# pmic_tps65263_buck.net
KiCad netlist of a schematic drawn in Altium Designer
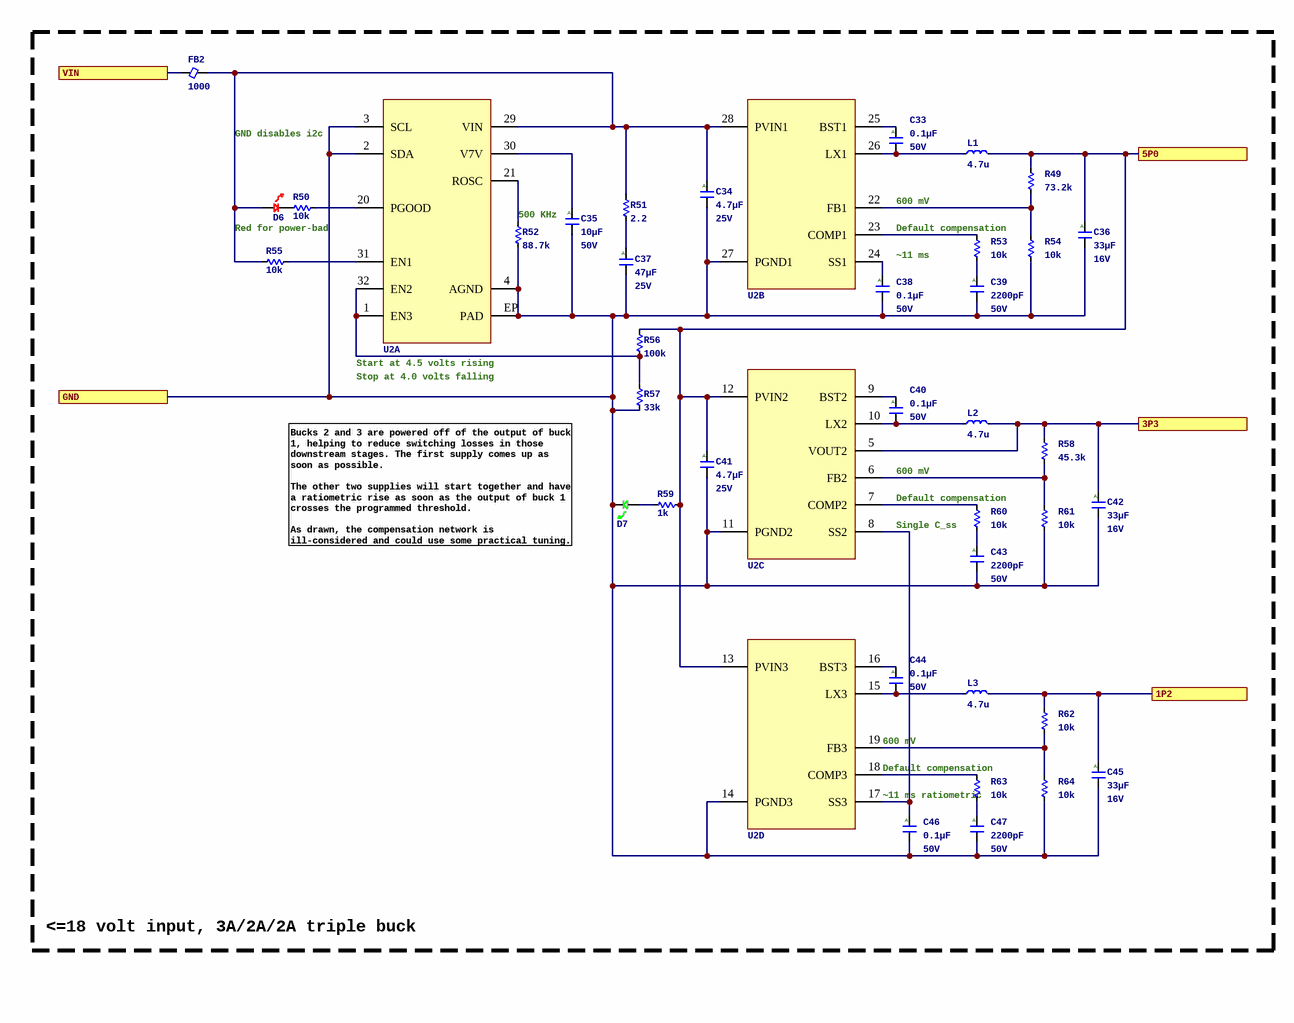
[diagram p0: pmic_tps65263_buck.SchDoc]

(export (version "E")
  (design (tool "Eeschema 10.0.6"))
  (components
    (comp (ref "C33")
      (value "CGA2B3X7R1H104M050BB")
      (footprint "C0402_0.55MM")
      (description "CAP CER 0.1UF 50V X7R 0402")
      (fields
        (field (name "CAPACITANCE") "0.1µF")
        (field (name "VOLTAGE - RATED") "50V")
        (field (name "TOLERANCE") "±20%")
        (field (name "MANUFACTURER") "TDK Corporation")
      )
      (libsource (lib "sscp") (part "__template_cap_auto"))
    )
    (comp (ref "C34")
      (value "CGA4J1X7R1E475K125AC")
      (footprint "C0805_1.45MM")
      (description "CAP CER 4.7UF 25V X7R 0805")
      (fields
        (field (name "CAPACITANCE") "4.7µF")
        (field (name "VOLTAGE - RATED") "25V")
        (field (name "TOLERANCE") "±10%")
        (field (name "MANUFACTURER") "TDK Corporation")
      )
      (libsource (lib "sscp") (part "__template_cap_auto"))
    )
    (comp (ref "C35")
      (value "CGA5L1X7R1H106K160AC")
      (footprint "C1206_1.90MM")
      (description "CAP CER 10UF 50V X7R 1206")
      (fields
        (field (name "CAPACITANCE") "10µF")
        (field (name "VOLTAGE - RATED") "50V")
        (field (name "TOLERANCE") "±10%")
        (field (name "MANUFACTURER") "TDK Corporation")
      )
      (libsource (lib "sscp") (part "__template_cap_auto"))
    )
    (comp (ref "C36")
      (value "CGA8P1X7R1C336M250KC")
      (footprint "C1812_2.50MM")
      (description "CAP CER 33UF 16V X7R 1812")
      (fields
        (field (name "CAPACITANCE") "33µF")
        (field (name "VOLTAGE - RATED") "16V")
        (field (name "TOLERANCE") "±20%")
        (field (name "MANUFACTURER") "TDK Corporation")
      )
      (libsource (lib "sscp") (part "__template_cap_auto"))
    )
    (comp (ref "C37")
      (value "CGA9N3X7R1E476M230KB")
      (footprint "C2220_2.50MM")
      (description "CAP CER 47UF 25V X7R 2220")
      (fields
        (field (name "CAPACITANCE") "47µF")
        (field (name "VOLTAGE - RATED") "25V")
        (field (name "TOLERANCE") "±20%")
        (field (name "MANUFACTURER") "TDK Corporation")
      )
      (libsource (lib "sscp") (part "__template_cap_auto"))
    )
    (comp (ref "C38")
      (value "CGA2B3X7R1H104M050BB")
      (footprint "C0402_0.55MM")
      (description "CAP CER 0.1UF 50V X7R 0402")
      (fields
        (field (name "CAPACITANCE") "0.1µF")
        (field (name "VOLTAGE - RATED") "50V")
        (field (name "TOLERANCE") "±20%")
        (field (name "MANUFACTURER") "TDK Corporation")
      )
      (libsource (lib "sscp") (part "__template_cap_auto"))
    )
    (comp (ref "C39")
      (value "CGA2B2X7R1H222M050BA")
      (footprint "C0402_0.55MM")
      (description "CAP CER 2200PF 50V X7R 0402")
      (fields
        (field (name "CAPACITANCE") "2200pF")
        (field (name "VOLTAGE - RATED") "50V")
        (field (name "TOLERANCE") "±20%")
        (field (name "MANUFACTURER") "TDK Corporation")
      )
      (libsource (lib "sscp") (part "__template_cap_auto"))
    )
    (comp (ref "C40")
      (value "CGA2B3X7R1H104M050BB")
      (footprint "C0402_0.55MM")
      (description "CAP CER 0.1UF 50V X7R 0402")
      (fields
        (field (name "CAPACITANCE") "0.1µF")
        (field (name "VOLTAGE - RATED") "50V")
        (field (name "TOLERANCE") "±20%")
        (field (name "MANUFACTURER") "TDK Corporation")
      )
      (libsource (lib "sscp") (part "__template_cap_auto"))
    )
    (comp (ref "C41")
      (value "CGA4J1X7R1E475K125AC")
      (footprint "C0805_1.45MM")
      (description "CAP CER 4.7UF 25V X7R 0805")
      (fields
        (field (name "CAPACITANCE") "4.7µF")
        (field (name "VOLTAGE - RATED") "25V")
        (field (name "TOLERANCE") "±10%")
        (field (name "MANUFACTURER") "TDK Corporation")
      )
      (libsource (lib "sscp") (part "__template_cap_auto"))
    )
    (comp (ref "C42")
      (value "CGA8P1X7R1C336M250KC")
      (footprint "C1812_2.50MM")
      (description "CAP CER 33UF 16V X7R 1812")
      (fields
        (field (name "CAPACITANCE") "33µF")
        (field (name "VOLTAGE - RATED") "16V")
        (field (name "TOLERANCE") "±20%")
        (field (name "MANUFACTURER") "TDK Corporation")
      )
      (libsource (lib "sscp") (part "__template_cap_auto"))
    )
    (comp (ref "C43")
      (value "CGA2B2X7R1H222M050BA")
      (footprint "C0402_0.55MM")
      (description "CAP CER 2200PF 50V X7R 0402")
      (fields
        (field (name "CAPACITANCE") "2200pF")
        (field (name "VOLTAGE - RATED") "50V")
        (field (name "TOLERANCE") "±20%")
        (field (name "MANUFACTURER") "TDK Corporation")
      )
      (libsource (lib "sscp") (part "__template_cap_auto"))
    )
    (comp (ref "C44")
      (value "CGA2B3X7R1H104M050BB")
      (footprint "C0402_0.55MM")
      (description "CAP CER 0.1UF 50V X7R 0402")
      (fields
        (field (name "CAPACITANCE") "0.1µF")
        (field (name "VOLTAGE - RATED") "50V")
        (field (name "TOLERANCE") "±20%")
        (field (name "MANUFACTURER") "TDK Corporation")
      )
      (libsource (lib "sscp") (part "__template_cap_auto"))
    )
    (comp (ref "C45")
      (value "CGA8P1X7R1C336M250KC")
      (footprint "C1812_2.50MM")
      (description "CAP CER 33UF 16V X7R 1812")
      (fields
        (field (name "CAPACITANCE") "33µF")
        (field (name "VOLTAGE - RATED") "16V")
        (field (name "TOLERANCE") "±20%")
        (field (name "MANUFACTURER") "TDK Corporation")
      )
      (libsource (lib "sscp") (part "__template_cap_auto"))
    )
    (comp (ref "C46")
      (value "CGA2B3X7R1H104M050BB")
      (footprint "C0402_0.55MM")
      (description "CAP CER 0.1UF 50V X7R 0402")
      (fields
        (field (name "CAPACITANCE") "0.1µF")
        (field (name "VOLTAGE - RATED") "50V")
        (field (name "TOLERANCE") "±20%")
        (field (name "MANUFACTURER") "TDK Corporation")
      )
      (libsource (lib "sscp") (part "__template_cap_auto"))
    )
    (comp (ref "C47")
      (value "CGA2B2X7R1H222M050BA")
      (footprint "C0402_0.55MM")
      (description "CAP CER 2200PF 50V X7R 0402")
      (fields
        (field (name "CAPACITANCE") "2200pF")
        (field (name "VOLTAGE - RATED") "50V")
        (field (name "TOLERANCE") "±20%")
        (field (name "MANUFACTURER") "TDK Corporation")
      )
      (libsource (lib "sscp") (part "__template_cap_auto"))
    )
    (comp (ref "D6")
      (value "LTST-C190KRKT")
      (footprint "LED_0603P_RED")
      (description "LED SUPER RED CLEAR 0603 SMD")
      (fields (field (name "MANUFACTURER") "Lite-On Inc"))
      (libsource (lib "SSCP") (part "LED_0603_RED_LTST-C190KRKT"))
    )
    (comp (ref "D7")
      (value "LTST-C190GKT")
      (footprint "LED_0603P_GREEN")
      (description "LED GREEN CLEAR 0603 SMD")
      (fields (field (name "MANUFACTURER") "Lite-On Inc"))
      (libsource (lib "SSCP") (part "LED_0603_GREEN_LTST-C190GKT"))
    )
    (comp (ref "FB2")
      (value "MPZ2012S102AT000")
      (footprint "FB0805_1.05MM")
      (description "FERRITE BEAD 1 KOHM 0805 1LN")
      (fields
        (field (name "IMPEDANCE (OHMS @ 100MHZ)") "1000")
        (field (name "MANUFACTURER") "TDK Corporation")
      )
      (libsource (lib "sscp") (part "__template_ferrite"))
    )
    (comp (ref "L1")
      (value "74438357047")
      (footprint "WE-MAPI_4030")
      (description "FIXED IND 4.7UH 3.9A 44 MOHM SMD")
      (fields
        (field (name "INDUCTANCE") "4.7u")
        (field (name "TOLERANCE") "±20%")
        (field (name "MANUFACTURER") "Würth Elektronik")
      )
      (libsource (lib "sscp") (part "__template_inductor"))
    )
    (comp (ref "L2")
      (value "74438357047")
      (footprint "WE-MAPI_4030")
      (description "FIXED IND 4.7UH 3.9A 44 MOHM SMD")
      (fields
        (field (name "INDUCTANCE") "4.7u")
        (field (name "TOLERANCE") "±20%")
        (field (name "MANUFACTURER") "Würth Elektronik")
      )
      (libsource (lib "sscp") (part "__template_inductor"))
    )
    (comp (ref "L3")
      (value "74438357047")
      (footprint "WE-MAPI_4030")
      (description "FIXED IND 4.7UH 3.9A 44 MOHM SMD")
      (fields
        (field (name "INDUCTANCE") "4.7u")
        (field (name "TOLERANCE") "±20%")
        (field (name "MANUFACTURER") "Würth Elektronik")
      )
      (libsource (lib "sscp") (part "__template_inductor"))
    )
    (comp (ref "R49")
      (value "ERJ-2RKF7322X")
      (footprint "R0402_0.40MM")
      (description "RES SMD 73.2K OHM 1% 1/10W 0402")
      (fields
        (field (name "RESISTANCE") "73.2k")
        (field (name "TOLERANCE") "±1%")
        (field (name "MANUFACTURER") "Panasonic Electronic Components")
      )
      (libsource (lib "sscp") (part "__template_resistor"))
    )
    (comp (ref "R50")
      (value "ERJ-2RKF1002X")
      (footprint "R0402_0.40MM")
      (description "RES SMD 10K OHM 1% 1/10W 0402")
      (fields
        (field (name "RESISTANCE") "10k")
        (field (name "TOLERANCE") "±1%")
        (field (name "MANUFACTURER") "Panasonic Electronic Components")
      )
      (libsource (lib "sscp") (part "__template_resistor"))
    )
    (comp (ref "R51")
      (value "ERJ-6DQF2R2V")
      (footprint "R0805_0.70MM")
      (description "RES SMD 2.2 OHM 1% 1/2W 0805")
      (fields
        (field (name "RESISTANCE") "2.2")
        (field (name "TOLERANCE") "±1%")
        (field (name "MANUFACTURER") "Panasonic Electronic Components")
      )
      (libsource (lib "sscp") (part "__template_resistor"))
    )
    (comp (ref "R52")
      (value "ERJ-2RKF8872X")
      (footprint "R0402_0.40MM")
      (description "RES SMD 88.7K OHM 1% 1/10W 0402")
      (fields
        (field (name "RESISTANCE") "88.7k")
        (field (name "TOLERANCE") "±1%")
        (field (name "MANUFACTURER") "Panasonic Electronic Components")
      )
      (libsource (lib "sscp") (part "__template_resistor"))
    )
    (comp (ref "R53")
      (value "ERJ-2RKF1002X")
      (footprint "R0402_0.40MM")
      (description "RES SMD 10K OHM 1% 1/10W 0402")
      (fields
        (field (name "RESISTANCE") "10k")
        (field (name "TOLERANCE") "±1%")
        (field (name "MANUFACTURER") "Panasonic Electronic Components")
      )
      (libsource (lib "sscp") (part "__template_resistor"))
    )
    (comp (ref "R54")
      (value "ERJ-2RKF1002X")
      (footprint "R0402_0.40MM")
      (description "RES SMD 10K OHM 1% 1/10W 0402")
      (fields
        (field (name "RESISTANCE") "10k")
        (field (name "TOLERANCE") "±1%")
        (field (name "MANUFACTURER") "Panasonic Electronic Components")
      )
      (libsource (lib "sscp") (part "__template_resistor"))
    )
    (comp (ref "R55")
      (value "ERJ-2RKF1002X")
      (footprint "R0402_0.40MM")
      (description "RES SMD 10K OHM 1% 1/10W 0402")
      (fields
        (field (name "RESISTANCE") "10k")
        (field (name "TOLERANCE") "±1%")
        (field (name "MANUFACTURER") "Panasonic Electronic Components")
      )
      (libsource (lib "sscp") (part "__template_resistor"))
    )
    (comp (ref "R56")
      (value "ERJ-2RKF1003X")
      (footprint "R0402_0.40MM")
      (description "RES SMD 100K OHM 1% 1/10W 0402")
      (fields
        (field (name "RESISTANCE") "100k")
        (field (name "TOLERANCE") "±1%")
        (field (name "MANUFACTURER") "Panasonic Electronic Components")
      )
      (libsource (lib "sscp") (part "__template_resistor"))
    )
    (comp (ref "R57")
      (value "ERJ-2RKF3302X")
      (footprint "R0402_0.40MM")
      (description "RES SMD 33K OHM 1% 1/10W 0402")
      (fields
        (field (name "RESISTANCE") "33k")
        (field (name "TOLERANCE") "±1%")
        (field (name "MANUFACTURER") "Panasonic Electronic Components")
      )
      (libsource (lib "sscp") (part "__template_resistor"))
    )
    (comp (ref "R58")
      (value "ERJ-2RKF4532X")
      (footprint "R0402_0.40MM")
      (description "RES SMD 45.3K OHM 1% 1/10W 0402")
      (fields
        (field (name "RESISTANCE") "45.3k")
        (field (name "TOLERANCE") "±1%")
        (field (name "MANUFACTURER") "Panasonic Electronic Components")
      )
      (libsource (lib "sscp") (part "__template_resistor"))
    )
    (comp (ref "R59")
      (value "~")
      (footprint "R0402_0.40MM")
      (description "RES SMD 1K OHM 1% 1/10W 0402")
      (fields (field (name "RESISTANCE") "1k") (field (name "TOLERANCE") "±1%"))
      (libsource (lib "sscp") (part "__template_resistor"))
    )
    (comp (ref "R60")
      (value "ERJ-2RKF1002X")
      (footprint "R0402_0.40MM")
      (description "RES SMD 10K OHM 1% 1/10W 0402")
      (fields
        (field (name "RESISTANCE") "10k")
        (field (name "TOLERANCE") "±1%")
        (field (name "MANUFACTURER") "Panasonic Electronic Components")
      )
      (libsource (lib "sscp") (part "__template_resistor"))
    )
    (comp (ref "R61")
      (value "ERJ-2RKF1002X")
      (footprint "R0402_0.40MM")
      (description "RES SMD 10K OHM 1% 1/10W 0402")
      (fields
        (field (name "RESISTANCE") "10k")
        (field (name "TOLERANCE") "±1%")
        (field (name "MANUFACTURER") "Panasonic Electronic Components")
      )
      (libsource (lib "sscp") (part "__template_resistor"))
    )
    (comp (ref "R62")
      (value "ERJ-2RKF1002X")
      (footprint "R0402_0.40MM")
      (description "RES SMD 10K OHM 1% 1/10W 0402")
      (fields
        (field (name "RESISTANCE") "10k")
        (field (name "TOLERANCE") "±1%")
        (field (name "MANUFACTURER") "Panasonic Electronic Components")
      )
      (libsource (lib "sscp") (part "__template_resistor"))
    )
    (comp (ref "R63")
      (value "ERJ-2RKF1002X")
      (footprint "R0402_0.40MM")
      (description "RES SMD 10K OHM 1% 1/10W 0402")
      (fields
        (field (name "RESISTANCE") "10k")
        (field (name "TOLERANCE") "±1%")
        (field (name "MANUFACTURER") "Panasonic Electronic Components")
      )
      (libsource (lib "sscp") (part "__template_resistor"))
    )
    (comp (ref "R64")
      (value "ERJ-2RKF1002X")
      (footprint "R0402_0.40MM")
      (description "RES SMD 10K OHM 1% 1/10W 0402")
      (fields
        (field (name "RESISTANCE") "10k")
        (field (name "TOLERANCE") "±1%")
        (field (name "MANUFACTURER") "Panasonic Electronic Components")
      )
      (libsource (lib "sscp") (part "__template_resistor"))
    )
    (comp (ref "U2")
      (value "TPS65263QRHBRQ1")
      (footprint "TI_RHB")
      (description "Switching Regulator, Current-mode, 3A, 2300kHz Switching Freq-Max, PQCC32")
      (fields (field (name "MANUFACTURER") "Texas Instruments"))
      (libsource (lib "SSCP") (part "BUCK_TPS65263QRHBRQ1"))
    )
  )
  (nets
    (net (code "1") (name "/1P2") (class "Default")
      (node (ref "C45") (pin "1") (pintype "passive"))
      (node (ref "L3") (pin "2") (pintype "passive"))
      (node (ref "R62") (pin "2") (pintype "passive"))
    )
    (net (code "2") (name "/3P3") (class "Default")
      (node (ref "C42") (pin "1") (pintype "passive"))
      (node (ref "L2") (pin "2") (pintype "passive"))
      (node (ref "R58") (pin "2") (pintype "passive"))
      (node (ref "U2") (pin "5") (pinfunction "VOUT2_5") (pintype "passive"))
    )
    (net (code "3") (name "/5P0") (class "Default")
      (node (ref "C36") (pin "1") (pintype "passive"))
      (node (ref "C41") (pin "1") (pintype "passive"))
      (node (ref "L1") (pin "2") (pintype "passive"))
      (node (ref "R49") (pin "2") (pintype "passive"))
      (node (ref "R56") (pin "2") (pintype "passive"))
      (node (ref "R59") (pin "1") (pintype "passive"))
      (node (ref "U2") (pin "12") (pinfunction "PVIN2_12") (pintype "passive"))
      (node (ref "U2") (pin "13") (pinfunction "PVIN3_13") (pintype "passive"))
    )
    (net (code "4") (name "/GND") (class "Default")
      (node (ref "C34") (pin "2") (pintype "passive"))
      (node (ref "C35") (pin "2") (pintype "passive"))
      (node (ref "C36") (pin "2") (pintype "passive"))
      (node (ref "C37") (pin "2") (pintype "passive"))
      (node (ref "C38") (pin "2") (pintype "passive"))
      (node (ref "C39") (pin "2") (pintype "passive"))
      (node (ref "C41") (pin "2") (pintype "passive"))
      (node (ref "C42") (pin "2") (pintype "passive"))
      (node (ref "C43") (pin "2") (pintype "passive"))
      (node (ref "C45") (pin "2") (pintype "passive"))
      (node (ref "C46") (pin "2") (pintype "passive"))
      (node (ref "C47") (pin "2") (pintype "passive"))
      (node (ref "D7") (pin "1") (pintype "passive"))
      (node (ref "R52") (pin "1") (pintype "passive"))
      (node (ref "R54") (pin "1") (pintype "passive"))
      (node (ref "R57") (pin "1") (pintype "passive"))
      (node (ref "R61") (pin "1") (pintype "passive"))
      (node (ref "R64") (pin "1") (pintype "passive"))
      (node (ref "U2") (pin "11") (pinfunction "PGND2_11") (pintype "passive"))
      (node (ref "U2") (pin "14") (pinfunction "PGND3_14") (pintype "passive"))
      (node (ref "U2") (pin "2") (pinfunction "SDA_2") (pintype "passive"))
      (node (ref "U2") (pin "27") (pinfunction "PGND1_27") (pintype "passive"))
      (node (ref "U2") (pin "3") (pinfunction "SCL_3") (pintype "passive"))
      (node (ref "U2") (pin "4") (pinfunction "AGND_4") (pintype "passive"))
      (node (ref "U2") (pin "EP") (pinfunction "PAD_EP") (pintype "passive"))
    )
    (net (code "5") (name "/VIN") (class "Default") (node (ref "FB2") (pin "1") (pintype "passive")))
    (net (code "6") (name "Net-(C37-Pad1)") (class "Default")
      (node (ref "C37") (pin "1") (pintype "passive"))
      (node (ref "R51") (pin "1") (pintype "passive"))
    )
    (net (code "7") (name "Net-(C39-Pad1)") (class "Default")
      (node (ref "C39") (pin "1") (pintype "passive"))
      (node (ref "R53") (pin "1") (pintype "passive"))
    )
    (net (code "8") (name "Net-(C43-Pad1)") (class "Default")
      (node (ref "C43") (pin "1") (pintype "passive"))
      (node (ref "R60") (pin "1") (pintype "passive"))
    )
    (net (code "9") (name "Net-(C47-Pad1)") (class "Default")
      (node (ref "C47") (pin "1") (pintype "passive"))
      (node (ref "R63") (pin "1") (pintype "passive"))
    )
    (net (code "10") (name "Net-(D6-Pad1)") (class "Default")
      (node (ref "D6") (pin "1") (pintype "passive"))
      (node (ref "R50") (pin "2") (pintype "passive"))
    )
    (net (code "11") (name "Net-(D7-Pad2)") (class "Default")
      (node (ref "D7") (pin "2") (pintype "passive"))
      (node (ref "R59") (pin "2") (pintype "passive"))
    )
    (net (code "12") (name "Net-(U2A-EN1)") (class "Default")
      (node (ref "R55") (pin "2") (pintype "passive"))
      (node (ref "U2") (pin "31") (pinfunction "EN1_31") (pintype "passive"))
    )
    (net (code "13") (name "Net-(U2A-EN2)") (class "Default")
      (node (ref "R56") (pin "1") (pintype "passive"))
      (node (ref "R57") (pin "2") (pintype "passive"))
      (node (ref "U2") (pin "1") (pinfunction "EN3_1") (pintype "passive"))
      (node (ref "U2") (pin "32") (pinfunction "EN2_32") (pintype "passive"))
    )
    (net (code "14") (name "Net-(U2A-PGOOD)") (class "Default")
      (node (ref "R50") (pin "1") (pintype "passive"))
      (node (ref "U2") (pin "20") (pinfunction "PGOOD_20") (pintype "passive"))
    )
    (net (code "15") (name "Net-(U2A-ROSC)") (class "Default")
      (node (ref "R52") (pin "2") (pintype "passive"))
      (node (ref "U2") (pin "21") (pinfunction "ROSC_21") (pintype "passive"))
    )
    (net (code "16") (name "Net-(U2A-V7V)") (class "Default")
      (node (ref "C35") (pin "1") (pintype "passive"))
      (node (ref "U2") (pin "30") (pinfunction "V7V_30") (pintype "passive"))
    )
    (net (code "17") (name "Net-(U2A-VIN)") (class "Default")
      (node (ref "C34") (pin "1") (pintype "passive"))
      (node (ref "D6") (pin "2") (pintype "passive"))
      (node (ref "FB2") (pin "2") (pintype "passive"))
      (node (ref "R51") (pin "2") (pintype "passive"))
      (node (ref "R55") (pin "1") (pintype "passive"))
      (node (ref "U2") (pin "28") (pinfunction "PVIN1_28") (pintype "passive"))
      (node (ref "U2") (pin "29") (pinfunction "VIN_29") (pintype "passive"))
    )
    (net (code "18") (name "Net-(U2B-BST1)") (class "Default")
      (node (ref "C33") (pin "1") (pintype "passive"))
      (node (ref "U2") (pin "25") (pinfunction "BST1_25") (pintype "passive"))
    )
    (net (code "19") (name "Net-(U2B-COMP1)") (class "Default")
      (node (ref "R53") (pin "2") (pintype "passive"))
      (node (ref "U2") (pin "23") (pinfunction "COMP1_23") (pintype "passive"))
    )
    (net (code "20") (name "Net-(U2B-FB1)") (class "Default")
      (node (ref "R49") (pin "1") (pintype "passive"))
      (node (ref "R54") (pin "2") (pintype "passive"))
      (node (ref "U2") (pin "22") (pinfunction "FB1_22") (pintype "passive"))
    )
    (net (code "21") (name "Net-(U2B-LX1)") (class "Default")
      (node (ref "C33") (pin "2") (pintype "passive"))
      (node (ref "L1") (pin "1") (pintype "passive"))
      (node (ref "U2") (pin "26") (pinfunction "LX1_26") (pintype "passive"))
    )
    (net (code "22") (name "Net-(U2B-SS1)") (class "Default")
      (node (ref "C38") (pin "1") (pintype "passive"))
      (node (ref "U2") (pin "24") (pinfunction "SS1_24") (pintype "passive"))
    )
    (net (code "23") (name "Net-(U2C-BST2)") (class "Default")
      (node (ref "C40") (pin "1") (pintype "passive"))
      (node (ref "U2") (pin "9") (pinfunction "BST2_9") (pintype "passive"))
    )
    (net (code "24") (name "Net-(U2C-COMP2)") (class "Default")
      (node (ref "R60") (pin "2") (pintype "passive"))
      (node (ref "U2") (pin "7") (pinfunction "COMP2_7") (pintype "passive"))
    )
    (net (code "25") (name "Net-(U2C-FB2)") (class "Default")
      (node (ref "R58") (pin "1") (pintype "passive"))
      (node (ref "R61") (pin "2") (pintype "passive"))
      (node (ref "U2") (pin "6") (pinfunction "FB2_6") (pintype "passive"))
    )
    (net (code "26") (name "Net-(U2C-LX2)") (class "Default")
      (node (ref "C40") (pin "2") (pintype "passive"))
      (node (ref "L2") (pin "1") (pintype "passive"))
      (node (ref "U2") (pin "10") (pinfunction "LX2_10") (pintype "passive"))
    )
    (net (code "27") (name "Net-(U2C-SS2)") (class "Default")
      (node (ref "C46") (pin "1") (pintype "passive"))
      (node (ref "U2") (pin "17") (pinfunction "SS3_17") (pintype "passive"))
      (node (ref "U2") (pin "8") (pinfunction "SS2_8") (pintype "passive"))
    )
    (net (code "28") (name "Net-(U2D-BST3)") (class "Default")
      (node (ref "C44") (pin "1") (pintype "passive"))
      (node (ref "U2") (pin "16") (pinfunction "BST3_16") (pintype "passive"))
    )
    (net (code "29") (name "Net-(U2D-COMP3)") (class "Default")
      (node (ref "R63") (pin "2") (pintype "passive"))
      (node (ref "U2") (pin "18") (pinfunction "COMP3_18") (pintype "passive"))
    )
    (net (code "30") (name "Net-(U2D-FB3)") (class "Default")
      (node (ref "R62") (pin "1") (pintype "passive"))
      (node (ref "R64") (pin "2") (pintype "passive"))
      (node (ref "U2") (pin "19") (pinfunction "FB3_19") (pintype "passive"))
    )
    (net (code "31") (name "Net-(U2D-LX3)") (class "Default")
      (node (ref "C44") (pin "2") (pintype "passive"))
      (node (ref "L3") (pin "1") (pintype "passive"))
      (node (ref "U2") (pin "15") (pinfunction "LX3_15") (pintype "passive"))
    )
  )
)
